# untitled.net
KiCad netlist of a schematic drawn in EAGLE
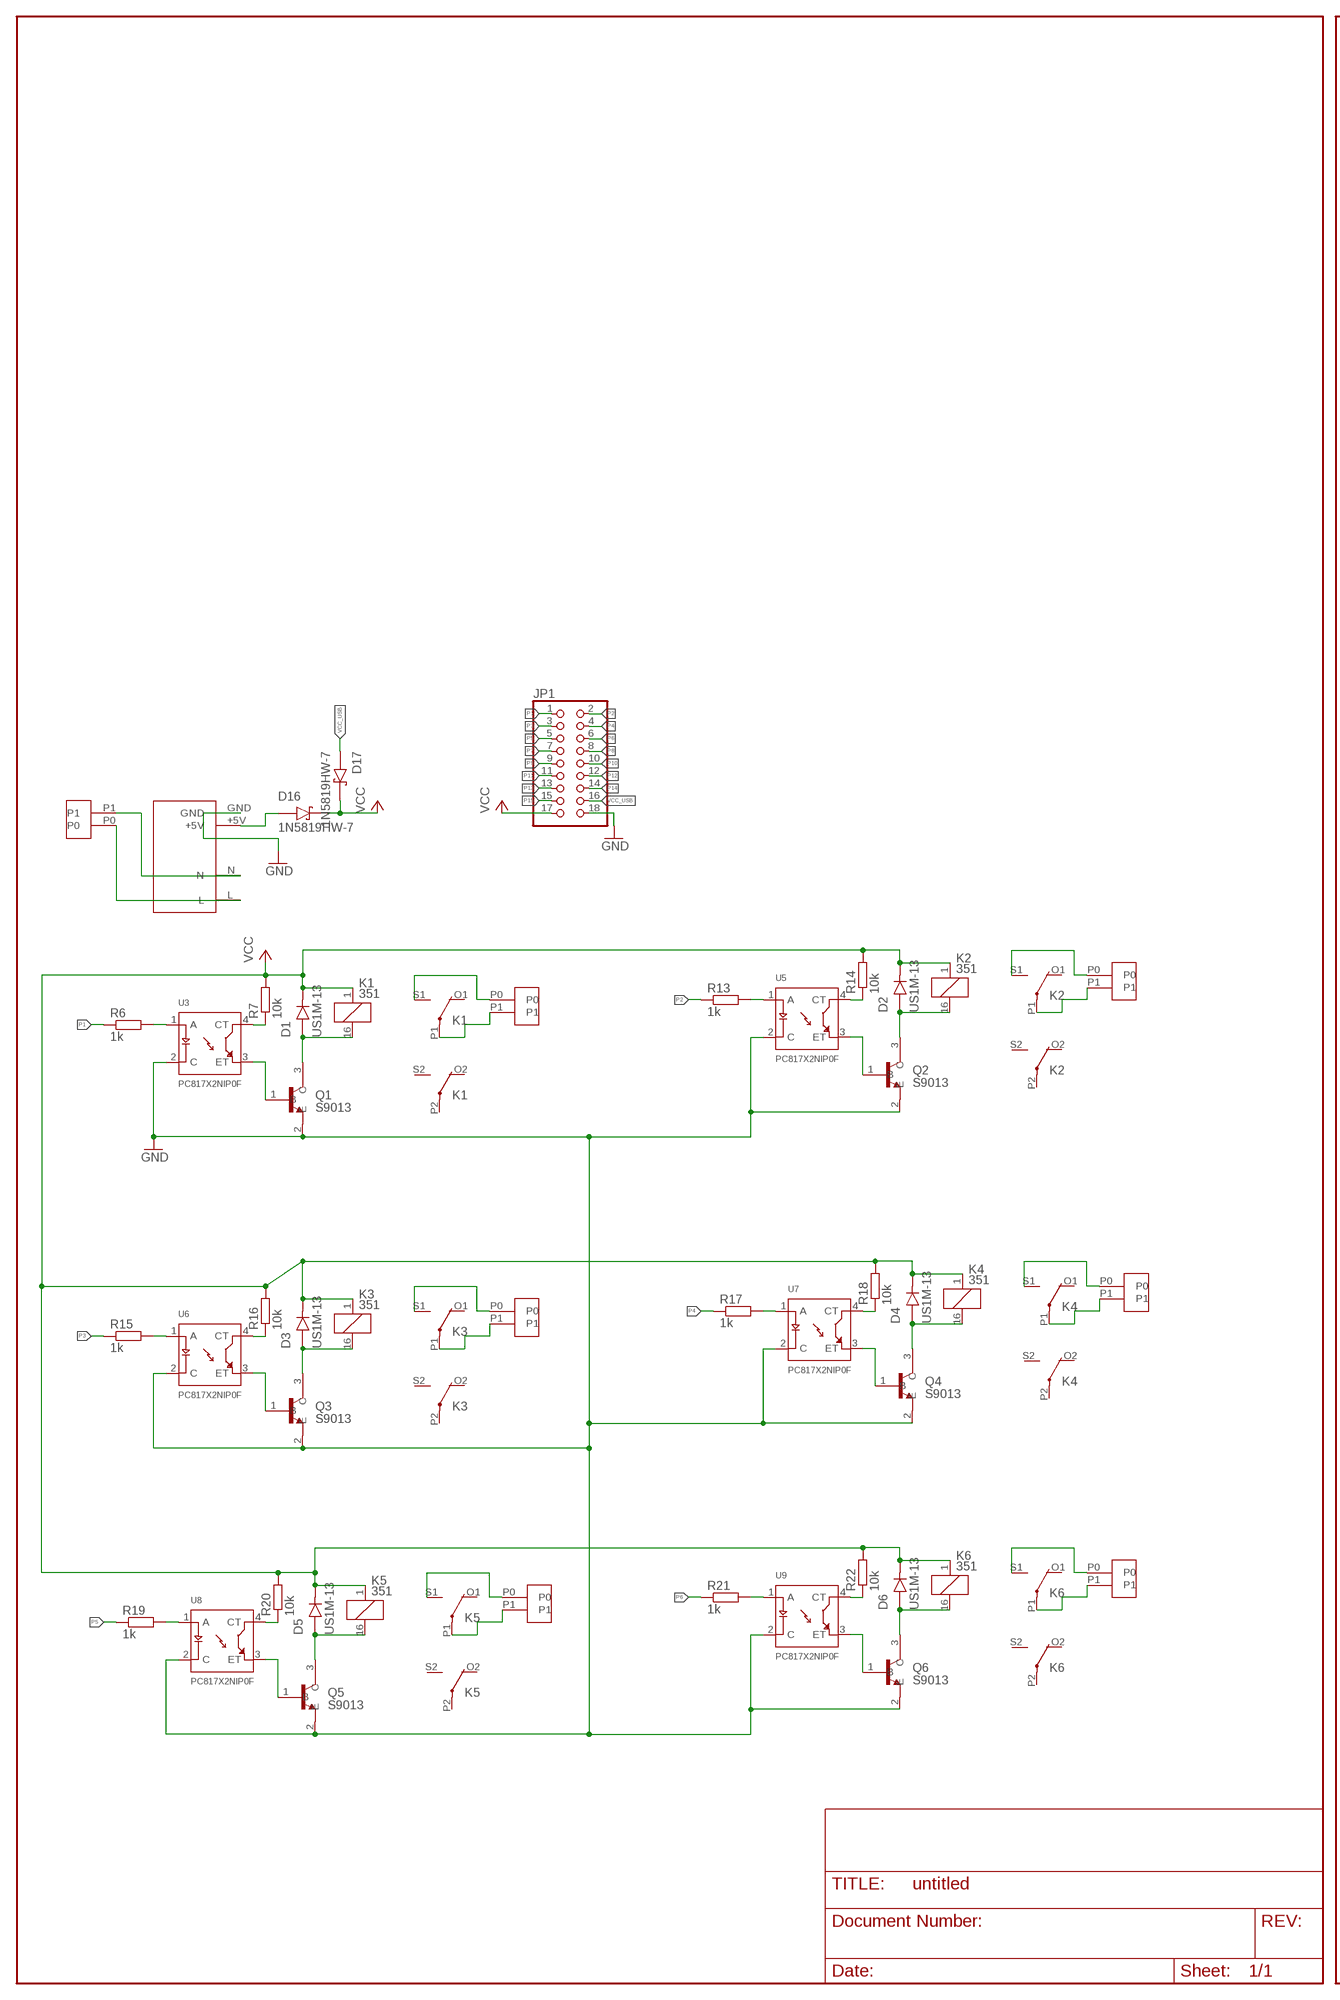
[diagram p0: schematic, sheet 1, part 1 of 2]
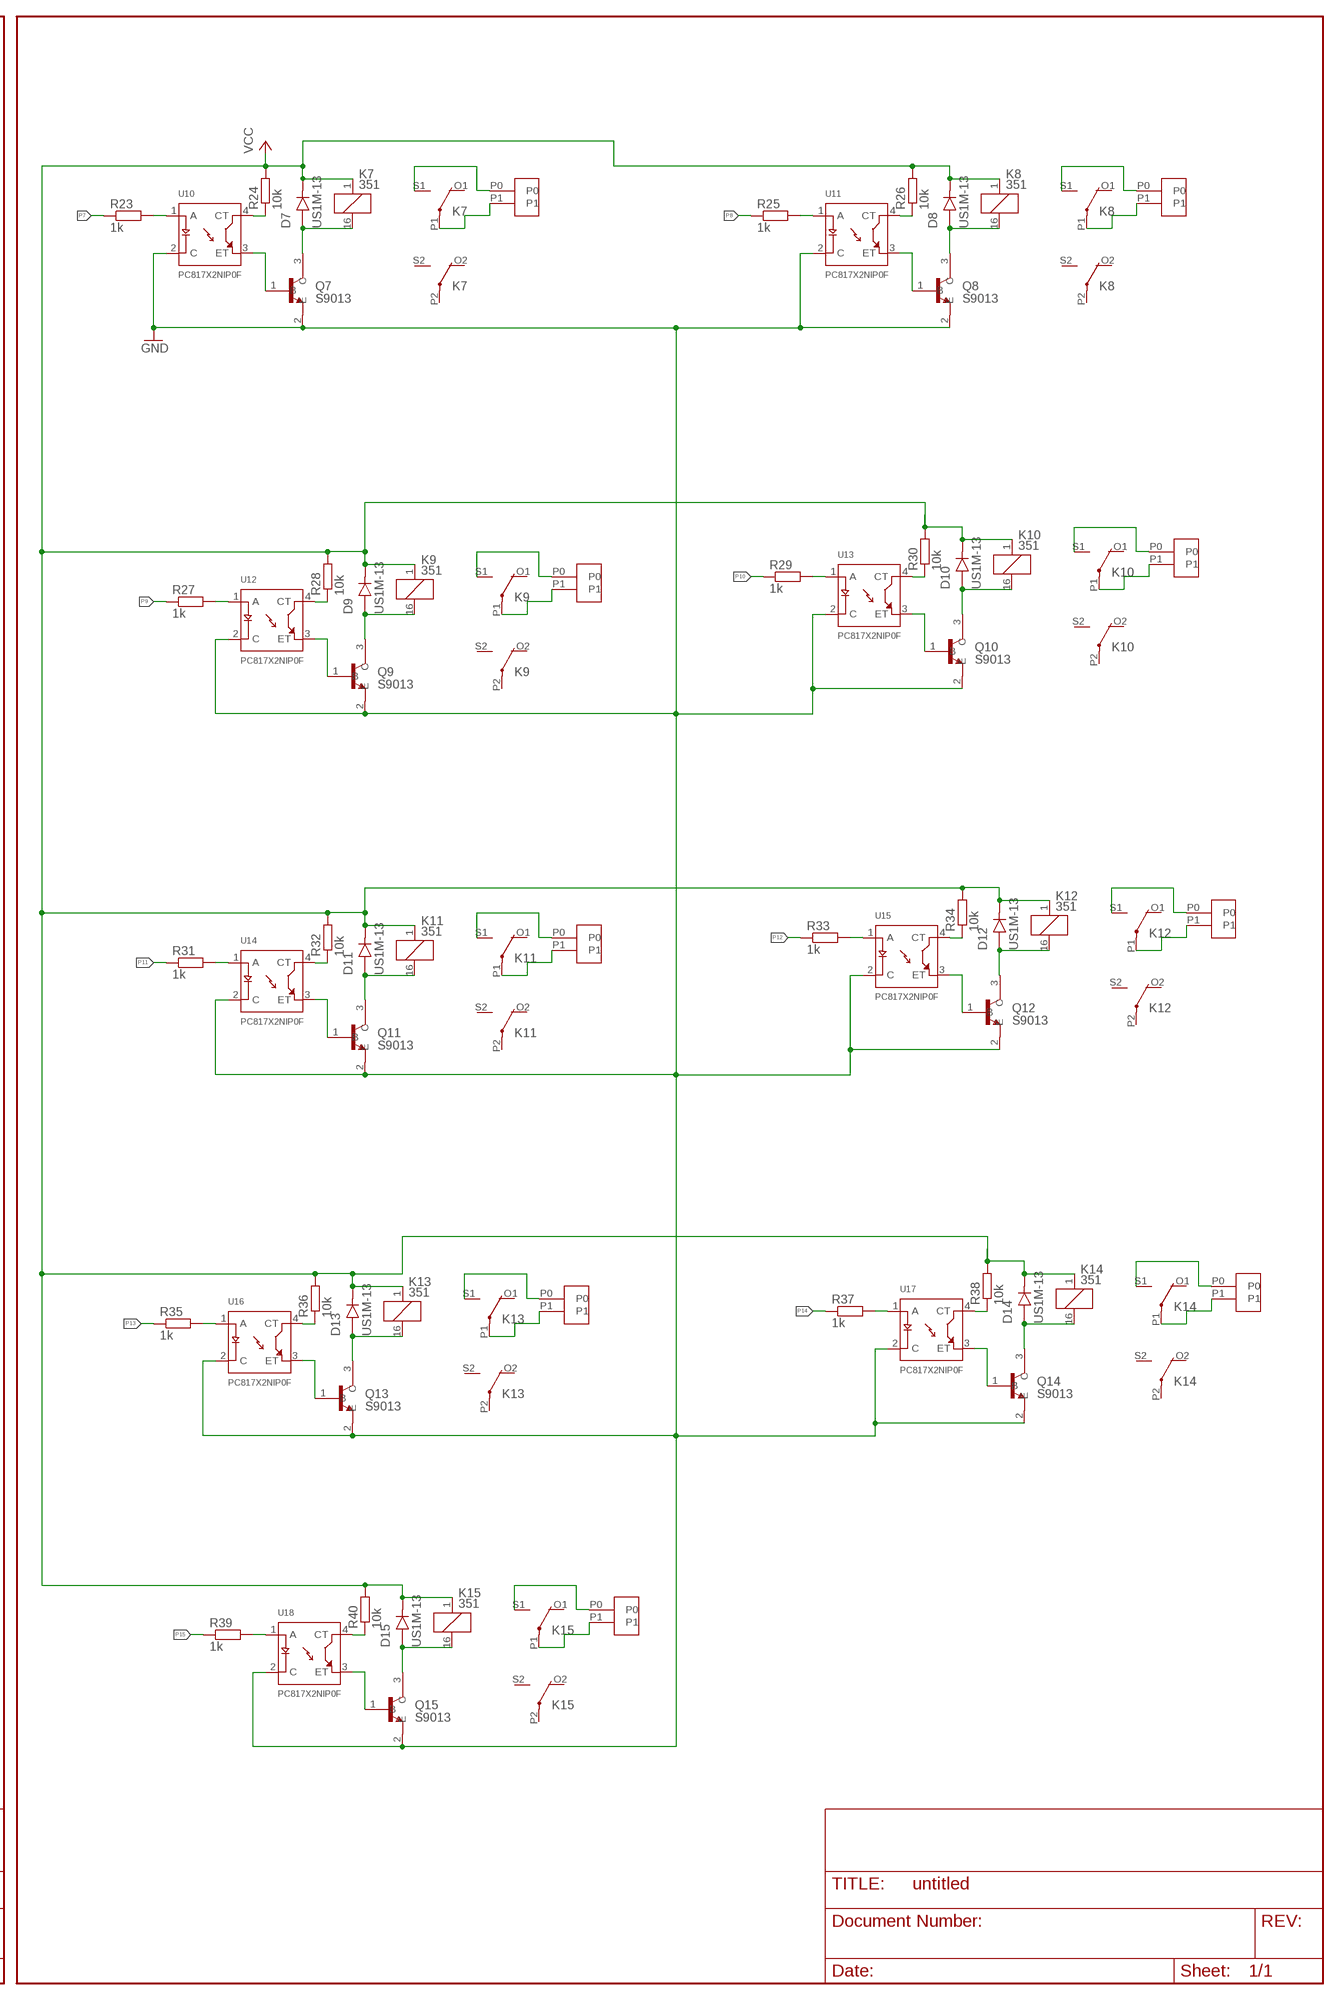
[diagram p1: schematic, sheet 1, part 2 of 2]

(export (version "E")
  (design (tool "Eeschema 10.0.6"))
  (components
    (comp (ref "CONN2P-3.5PI1")
      (value "CONN2P-3.5PI")
      (footprint "eagle-import:CONN2P-3.5PI")
      (libsource (lib "eagle-import") (part "CONN2P-3.5PI"))
    )
    (comp (ref "CONN2P-3.5PI2")
      (value "CONN2P-3.5PI")
      (footprint "eagle-import:CONN2P-3.5PI")
      (libsource (lib "eagle-import") (part "CONN2P-3.5PI"))
    )
    (comp (ref "CONN2P-3.5PI3")
      (value "CONN2P-3.5PI")
      (footprint "eagle-import:CONN2P-3.5PI")
      (libsource (lib "eagle-import") (part "CONN2P-3.5PI"))
    )
    (comp (ref "CONN2P-3.5PI4")
      (value "CONN2P-3.5PI")
      (footprint "eagle-import:CONN2P-3.5PI")
      (libsource (lib "eagle-import") (part "CONN2P-3.5PI"))
    )
    (comp (ref "CONN2P-3.5PI5")
      (value "CONN2P-3.5PI")
      (footprint "eagle-import:CONN2P-3.5PI")
      (libsource (lib "eagle-import") (part "CONN2P-3.5PI"))
    )
    (comp (ref "CONN2P-3.5PI6")
      (value "CONN2P-3.5PI")
      (footprint "eagle-import:CONN2P-3.5PI")
      (libsource (lib "eagle-import") (part "CONN2P-3.5PI"))
    )
    (comp (ref "CONN2P-3.5PI7")
      (value "CONN2P-3.5PI")
      (footprint "eagle-import:CONN2P-3.5PI")
      (libsource (lib "eagle-import") (part "CONN2P-3.5PI"))
    )
    (comp (ref "CONN2P-3.5PI8")
      (value "CONN2P-3.5PI")
      (footprint "eagle-import:CONN2P-3.5PI")
      (libsource (lib "eagle-import") (part "CONN2P-3.5PI"))
    )
    (comp (ref "CONN2P-3.5PI9")
      (value "CONN2P-3.5PI")
      (footprint "eagle-import:CONN2P-3.5PI")
      (libsource (lib "eagle-import") (part "CONN2P-3.5PI"))
    )
    (comp (ref "CONN2P-3.5PI10")
      (value "CONN2P-3.5PI")
      (footprint "eagle-import:CONN2P-3.5PI")
      (libsource (lib "eagle-import") (part "CONN2P-3.5PI"))
    )
    (comp (ref "CONN2P-3.5PI11")
      (value "CONN2P-3.5PI")
      (footprint "eagle-import:CONN2P-3.5PI")
      (libsource (lib "eagle-import") (part "CONN2P-3.5PI"))
    )
    (comp (ref "CONN2P-3.5PI12")
      (value "CONN2P-3.5PI")
      (footprint "eagle-import:CONN2P-3.5PI")
      (libsource (lib "eagle-import") (part "CONN2P-3.5PI"))
    )
    (comp (ref "CONN2P-3.5PI13")
      (value "CONN2P-3.5PI")
      (footprint "eagle-import:CONN2P-3.5PI")
      (libsource (lib "eagle-import") (part "CONN2P-3.5PI"))
    )
    (comp (ref "CONN2P-3.5PI14")
      (value "CONN2P-3.5PI")
      (footprint "eagle-import:CONN2P-3.5PI")
      (libsource (lib "eagle-import") (part "CONN2P-3.5PI"))
    )
    (comp (ref "CONN2P-3.5PI15")
      (value "CONN2P-3.5PI")
      (footprint "eagle-import:CONN2P-3.5PI")
      (libsource (lib "eagle-import") (part "CONN2P-3.5PI"))
    )
    (comp (ref "CONN2P-3.5PI16")
      (value "CONN2P-3.5PI")
      (footprint "eagle-import:CONN2P-3.5PI")
      (libsource (lib "eagle-import") (part "CONN2P-3.5PI"))
    )
    (comp (ref "D1")
      (value "US1M-13")
      (footprint "eagle-import:DIOM5226X240N")
      (fields (field (name "MF") "Diodes Incorporated"))
      (libsource (lib "eagle-import") (part "US1M-13"))
    )
    (comp (ref "D2")
      (value "US1M-13")
      (footprint "eagle-import:DIOM5226X240N")
      (fields (field (name "MF") "Diodes Incorporated"))
      (libsource (lib "eagle-import") (part "US1M-13"))
    )
    (comp (ref "D3")
      (value "US1M-13")
      (footprint "eagle-import:DIOM5226X240N")
      (fields (field (name "MF") "Diodes Incorporated"))
      (libsource (lib "eagle-import") (part "US1M-13"))
    )
    (comp (ref "D4")
      (value "US1M-13")
      (footprint "eagle-import:DIOM5226X240N")
      (fields (field (name "MF") "Diodes Incorporated"))
      (libsource (lib "eagle-import") (part "US1M-13"))
    )
    (comp (ref "D5")
      (value "US1M-13")
      (footprint "eagle-import:DIOM5226X240N")
      (fields (field (name "MF") "Diodes Incorporated"))
      (libsource (lib "eagle-import") (part "US1M-13"))
    )
    (comp (ref "D6")
      (value "US1M-13")
      (footprint "eagle-import:DIOM5226X240N")
      (fields (field (name "MF") "Diodes Incorporated"))
      (libsource (lib "eagle-import") (part "US1M-13"))
    )
    (comp (ref "D7")
      (value "US1M-13")
      (footprint "eagle-import:DIOM5226X240N")
      (fields (field (name "MF") "Diodes Incorporated"))
      (libsource (lib "eagle-import") (part "US1M-13"))
    )
    (comp (ref "D8")
      (value "US1M-13")
      (footprint "eagle-import:DIOM5226X240N")
      (fields (field (name "MF") "Diodes Incorporated"))
      (libsource (lib "eagle-import") (part "US1M-13"))
    )
    (comp (ref "D9")
      (value "US1M-13")
      (footprint "eagle-import:DIOM5226X240N")
      (fields (field (name "MF") "Diodes Incorporated"))
      (libsource (lib "eagle-import") (part "US1M-13"))
    )
    (comp (ref "D10")
      (value "US1M-13")
      (footprint "eagle-import:DIOM5226X240N")
      (fields (field (name "MF") "Diodes Incorporated"))
      (libsource (lib "eagle-import") (part "US1M-13"))
    )
    (comp (ref "D11")
      (value "US1M-13")
      (footprint "eagle-import:DIOM5226X240N")
      (fields (field (name "MF") "Diodes Incorporated"))
      (libsource (lib "eagle-import") (part "US1M-13"))
    )
    (comp (ref "D12")
      (value "US1M-13")
      (footprint "eagle-import:DIOM5226X240N")
      (fields (field (name "MF") "Diodes Incorporated"))
      (libsource (lib "eagle-import") (part "US1M-13"))
    )
    (comp (ref "D13")
      (value "US1M-13")
      (footprint "eagle-import:DIOM5226X240N")
      (fields (field (name "MF") "Diodes Incorporated"))
      (libsource (lib "eagle-import") (part "US1M-13"))
    )
    (comp (ref "D14")
      (value "US1M-13")
      (footprint "eagle-import:DIOM5226X240N")
      (fields (field (name "MF") "Diodes Incorporated"))
      (libsource (lib "eagle-import") (part "US1M-13"))
    )
    (comp (ref "D15")
      (value "US1M-13")
      (footprint "eagle-import:DIOM5226X240N")
      (fields (field (name "MF") "Diodes Incorporated"))
      (libsource (lib "eagle-import") (part "US1M-13"))
    )
    (comp (ref "D16")
      (value "1N5819HW-7")
      (footprint "eagle-import:SOD3715X145N")
      (fields (field (name "MF") "Diodes Inc."))
      (libsource (lib "eagle-import") (part "1N5819HW-7"))
    )
    (comp (ref "D17")
      (value "1N5819HW-7")
      (footprint "eagle-import:SOD3715X145N")
      (fields (field (name "MF") "Diodes Inc."))
      (libsource (lib "eagle-import") (part "1N5819HW-7"))
    )
    (comp (ref "JP1")
      (value "PINHD-2X9-CBIG")
      (footprint "eagle-import:2X09-CLEANBIG")
      (libsource (lib "eagle-import") (part "PINHD-2X9-CBIG"))
    )
    (comp (ref "K1")
      (value "351")
      (footprint "eagle-import:351")
      (libsource (lib "eagle-import") (part "351"))
    )
    (comp (ref "K2")
      (value "351")
      (footprint "eagle-import:351")
      (libsource (lib "eagle-import") (part "351"))
    )
    (comp (ref "K3")
      (value "351")
      (footprint "eagle-import:351")
      (libsource (lib "eagle-import") (part "351"))
    )
    (comp (ref "K4")
      (value "351")
      (footprint "eagle-import:351")
      (libsource (lib "eagle-import") (part "351"))
    )
    (comp (ref "K5")
      (value "351")
      (footprint "eagle-import:351")
      (libsource (lib "eagle-import") (part "351"))
    )
    (comp (ref "K6")
      (value "351")
      (footprint "eagle-import:351")
      (libsource (lib "eagle-import") (part "351"))
    )
    (comp (ref "K7")
      (value "351")
      (footprint "eagle-import:351")
      (libsource (lib "eagle-import") (part "351"))
    )
    (comp (ref "K8")
      (value "351")
      (footprint "eagle-import:351")
      (libsource (lib "eagle-import") (part "351"))
    )
    (comp (ref "K9")
      (value "351")
      (footprint "eagle-import:351")
      (libsource (lib "eagle-import") (part "351"))
    )
    (comp (ref "K10")
      (value "351")
      (footprint "eagle-import:351")
      (libsource (lib "eagle-import") (part "351"))
    )
    (comp (ref "K11")
      (value "351")
      (footprint "eagle-import:351")
      (libsource (lib "eagle-import") (part "351"))
    )
    (comp (ref "K12")
      (value "351")
      (footprint "eagle-import:351")
      (libsource (lib "eagle-import") (part "351"))
    )
    (comp (ref "K13")
      (value "351")
      (footprint "eagle-import:351")
      (libsource (lib "eagle-import") (part "351"))
    )
    (comp (ref "K14")
      (value "351")
      (footprint "eagle-import:351")
      (libsource (lib "eagle-import") (part "351"))
    )
    (comp (ref "K15")
      (value "351")
      (footprint "eagle-import:351")
      (libsource (lib "eagle-import") (part "351"))
    )
    (comp (ref "Q1")
      (value "S9013")
      (footprint "eagle-import:SOT95P240X120-3N")
      (fields (field (name "MF") "JCET"))
      (libsource (lib "eagle-import") (part "S9013"))
    )
    (comp (ref "Q2")
      (value "S9013")
      (footprint "eagle-import:SOT95P240X120-3N")
      (fields (field (name "MF") "JCET"))
      (libsource (lib "eagle-import") (part "S9013"))
    )
    (comp (ref "Q3")
      (value "S9013")
      (footprint "eagle-import:SOT95P240X120-3N")
      (fields (field (name "MF") "JCET"))
      (libsource (lib "eagle-import") (part "S9013"))
    )
    (comp (ref "Q4")
      (value "S9013")
      (footprint "eagle-import:SOT95P240X120-3N")
      (fields (field (name "MF") "JCET"))
      (libsource (lib "eagle-import") (part "S9013"))
    )
    (comp (ref "Q5")
      (value "S9013")
      (footprint "eagle-import:SOT95P240X120-3N")
      (fields (field (name "MF") "JCET"))
      (libsource (lib "eagle-import") (part "S9013"))
    )
    (comp (ref "Q6")
      (value "S9013")
      (footprint "eagle-import:SOT95P240X120-3N")
      (fields (field (name "MF") "JCET"))
      (libsource (lib "eagle-import") (part "S9013"))
    )
    (comp (ref "Q7")
      (value "S9013")
      (footprint "eagle-import:SOT95P240X120-3N")
      (fields (field (name "MF") "JCET"))
      (libsource (lib "eagle-import") (part "S9013"))
    )
    (comp (ref "Q8")
      (value "S9013")
      (footprint "eagle-import:SOT95P240X120-3N")
      (fields (field (name "MF") "JCET"))
      (libsource (lib "eagle-import") (part "S9013"))
    )
    (comp (ref "Q9")
      (value "S9013")
      (footprint "eagle-import:SOT95P240X120-3N")
      (fields (field (name "MF") "JCET"))
      (libsource (lib "eagle-import") (part "S9013"))
    )
    (comp (ref "Q10")
      (value "S9013")
      (footprint "eagle-import:SOT95P240X120-3N")
      (fields (field (name "MF") "JCET"))
      (libsource (lib "eagle-import") (part "S9013"))
    )
    (comp (ref "Q11")
      (value "S9013")
      (footprint "eagle-import:SOT95P240X120-3N")
      (fields (field (name "MF") "JCET"))
      (libsource (lib "eagle-import") (part "S9013"))
    )
    (comp (ref "Q12")
      (value "S9013")
      (footprint "eagle-import:SOT95P240X120-3N")
      (fields (field (name "MF") "JCET"))
      (libsource (lib "eagle-import") (part "S9013"))
    )
    (comp (ref "Q13")
      (value "S9013")
      (footprint "eagle-import:SOT95P240X120-3N")
      (fields (field (name "MF") "JCET"))
      (libsource (lib "eagle-import") (part "S9013"))
    )
    (comp (ref "Q14")
      (value "S9013")
      (footprint "eagle-import:SOT95P240X120-3N")
      (fields (field (name "MF") "JCET"))
      (libsource (lib "eagle-import") (part "S9013"))
    )
    (comp (ref "Q15")
      (value "S9013")
      (footprint "eagle-import:SOT95P240X120-3N")
      (fields (field (name "MF") "JCET"))
      (libsource (lib "eagle-import") (part "S9013"))
    )
    (comp (ref "R6")
      (value "1k")
      (footprint "eagle-import:R0805")
      (libsource (lib "eagle-import") (part "R-EU_R0805"))
    )
    (comp (ref "R7")
      (value "10k")
      (footprint "eagle-import:R0805")
      (libsource (lib "eagle-import") (part "R-EU_R0805"))
    )
    (comp (ref "R13")
      (value "1k")
      (footprint "eagle-import:R0805")
      (libsource (lib "eagle-import") (part "R-EU_R0805"))
    )
    (comp (ref "R14")
      (value "10k")
      (footprint "eagle-import:R0805")
      (libsource (lib "eagle-import") (part "R-EU_R0805"))
    )
    (comp (ref "R15")
      (value "1k")
      (footprint "eagle-import:R0805")
      (libsource (lib "eagle-import") (part "R-EU_R0805"))
    )
    (comp (ref "R16")
      (value "10k")
      (footprint "eagle-import:R0805")
      (libsource (lib "eagle-import") (part "R-EU_R0805"))
    )
    (comp (ref "R17")
      (value "1k")
      (footprint "eagle-import:R0805")
      (libsource (lib "eagle-import") (part "R-EU_R0805"))
    )
    (comp (ref "R18")
      (value "10k")
      (footprint "eagle-import:R0805")
      (libsource (lib "eagle-import") (part "R-EU_R0805"))
    )
    (comp (ref "R19")
      (value "1k")
      (footprint "eagle-import:R0805")
      (libsource (lib "eagle-import") (part "R-EU_R0805"))
    )
    (comp (ref "R20")
      (value "10k")
      (footprint "eagle-import:R0805")
      (libsource (lib "eagle-import") (part "R-EU_R0805"))
    )
    (comp (ref "R21")
      (value "1k")
      (footprint "eagle-import:R0805")
      (libsource (lib "eagle-import") (part "R-EU_R0805"))
    )
    (comp (ref "R22")
      (value "10k")
      (footprint "eagle-import:R0805")
      (libsource (lib "eagle-import") (part "R-EU_R0805"))
    )
    (comp (ref "R23")
      (value "1k")
      (footprint "eagle-import:R0805")
      (libsource (lib "eagle-import") (part "R-EU_R0805"))
    )
    (comp (ref "R24")
      (value "10k")
      (footprint "eagle-import:R0805")
      (libsource (lib "eagle-import") (part "R-EU_R0805"))
    )
    (comp (ref "R25")
      (value "1k")
      (footprint "eagle-import:R0805")
      (libsource (lib "eagle-import") (part "R-EU_R0805"))
    )
    (comp (ref "R26")
      (value "10k")
      (footprint "eagle-import:R0805")
      (libsource (lib "eagle-import") (part "R-EU_R0805"))
    )
    (comp (ref "R27")
      (value "1k")
      (footprint "eagle-import:R0805")
      (libsource (lib "eagle-import") (part "R-EU_R0805"))
    )
    (comp (ref "R28")
      (value "10k")
      (footprint "eagle-import:R0805")
      (libsource (lib "eagle-import") (part "R-EU_R0805"))
    )
    (comp (ref "R29")
      (value "1k")
      (footprint "eagle-import:R0805")
      (libsource (lib "eagle-import") (part "R-EU_R0805"))
    )
    (comp (ref "R30")
      (value "10k")
      (footprint "eagle-import:R0805")
      (libsource (lib "eagle-import") (part "R-EU_R0805"))
    )
    (comp (ref "R31")
      (value "1k")
      (footprint "eagle-import:R0805")
      (libsource (lib "eagle-import") (part "R-EU_R0805"))
    )
    (comp (ref "R32")
      (value "10k")
      (footprint "eagle-import:R0805")
      (libsource (lib "eagle-import") (part "R-EU_R0805"))
    )
    (comp (ref "R33")
      (value "1k")
      (footprint "eagle-import:R0805")
      (libsource (lib "eagle-import") (part "R-EU_R0805"))
    )
    (comp (ref "R34")
      (value "10k")
      (footprint "eagle-import:R0805")
      (libsource (lib "eagle-import") (part "R-EU_R0805"))
    )
    (comp (ref "R35")
      (value "1k")
      (footprint "eagle-import:R0805")
      (libsource (lib "eagle-import") (part "R-EU_R0805"))
    )
    (comp (ref "R36")
      (value "10k")
      (footprint "eagle-import:R0805")
      (libsource (lib "eagle-import") (part "R-EU_R0805"))
    )
    (comp (ref "R37")
      (value "1k")
      (footprint "eagle-import:R0805")
      (libsource (lib "eagle-import") (part "R-EU_R0805"))
    )
    (comp (ref "R38")
      (value "10k")
      (footprint "eagle-import:R0805")
      (libsource (lib "eagle-import") (part "R-EU_R0805"))
    )
    (comp (ref "R39")
      (value "1k")
      (footprint "eagle-import:R0805")
      (libsource (lib "eagle-import") (part "R-EU_R0805"))
    )
    (comp (ref "R40")
      (value "10k")
      (footprint "eagle-import:R0805")
      (libsource (lib "eagle-import") (part "R-EU_R0805"))
    )
    (comp (ref "U3")
      (value "PC817X2NIP0F")
      (footprint "eagle-import:SOT254P975X400-4N")
      (fields (field (name "MF") "Sharp Microelectronics"))
      (libsource (lib "eagle-import") (part "PC817X2NIP0F"))
    )
    (comp (ref "U5")
      (value "PC817X2NIP0F")
      (footprint "eagle-import:SOT254P975X400-4N")
      (fields (field (name "MF") "Sharp Microelectronics"))
      (libsource (lib "eagle-import") (part "PC817X2NIP0F"))
    )
    (comp (ref "U6")
      (value "PC817X2NIP0F")
      (footprint "eagle-import:SOT254P975X400-4N")
      (fields (field (name "MF") "Sharp Microelectronics"))
      (libsource (lib "eagle-import") (part "PC817X2NIP0F"))
    )
    (comp (ref "U7")
      (value "PC817X2NIP0F")
      (footprint "eagle-import:SOT254P975X400-4N")
      (fields (field (name "MF") "Sharp Microelectronics"))
      (libsource (lib "eagle-import") (part "PC817X2NIP0F"))
    )
    (comp (ref "U8")
      (value "PC817X2NIP0F")
      (footprint "eagle-import:SOT254P975X400-4N")
      (fields (field (name "MF") "Sharp Microelectronics"))
      (libsource (lib "eagle-import") (part "PC817X2NIP0F"))
    )
    (comp (ref "U9")
      (value "PC817X2NIP0F")
      (footprint "eagle-import:SOT254P975X400-4N")
      (fields (field (name "MF") "Sharp Microelectronics"))
      (libsource (lib "eagle-import") (part "PC817X2NIP0F"))
    )
    (comp (ref "U10")
      (value "PC817X2NIP0F")
      (footprint "eagle-import:SOT254P975X400-4N")
      (fields (field (name "MF") "Sharp Microelectronics"))
      (libsource (lib "eagle-import") (part "PC817X2NIP0F"))
    )
    (comp (ref "U11")
      (value "PC817X2NIP0F")
      (footprint "eagle-import:SOT254P975X400-4N")
      (fields (field (name "MF") "Sharp Microelectronics"))
      (libsource (lib "eagle-import") (part "PC817X2NIP0F"))
    )
    (comp (ref "U12")
      (value "PC817X2NIP0F")
      (footprint "eagle-import:SOT254P975X400-4N")
      (fields (field (name "MF") "Sharp Microelectronics"))
      (libsource (lib "eagle-import") (part "PC817X2NIP0F"))
    )
    (comp (ref "U13")
      (value "PC817X2NIP0F")
      (footprint "eagle-import:SOT254P975X400-4N")
      (fields (field (name "MF") "Sharp Microelectronics"))
      (libsource (lib "eagle-import") (part "PC817X2NIP0F"))
    )
    (comp (ref "U14")
      (value "PC817X2NIP0F")
      (footprint "eagle-import:SOT254P975X400-4N")
      (fields (field (name "MF") "Sharp Microelectronics"))
      (libsource (lib "eagle-import") (part "PC817X2NIP0F"))
    )
    (comp (ref "U15")
      (value "PC817X2NIP0F")
      (footprint "eagle-import:SOT254P975X400-4N")
      (fields (field (name "MF") "Sharp Microelectronics"))
      (libsource (lib "eagle-import") (part "PC817X2NIP0F"))
    )
    (comp (ref "U16")
      (value "PC817X2NIP0F")
      (footprint "eagle-import:SOT254P975X400-4N")
      (fields (field (name "MF") "Sharp Microelectronics"))
      (libsource (lib "eagle-import") (part "PC817X2NIP0F"))
    )
    (comp (ref "U17")
      (value "PC817X2NIP0F")
      (footprint "eagle-import:SOT254P975X400-4N")
      (fields (field (name "MF") "Sharp Microelectronics"))
      (libsource (lib "eagle-import") (part "PC817X2NIP0F"))
    )
    (comp (ref "U18")
      (value "PC817X2NIP0F")
      (footprint "eagle-import:SOT254P975X400-4N")
      (fields (field (name "MF") "Sharp Microelectronics"))
      (libsource (lib "eagle-import") (part "PC817X2NIP0F"))
    )
    (comp (ref "WX-DC1")
      (value "WX-DC12003")
      (footprint "eagle-import:WX-DC12003")
      (libsource (lib "eagle-import") (part "WX-DC12003"))
    )
  )
  (nets
    (net (code "1") (name "GND") (class "Default")
      (node (ref "JP1") (pin "18") (pinfunction "18_18") (pintype "passive"))
      (node (ref "Q1") (pin "2") (pinfunction "E_2") (pintype "passive"))
      (node (ref "Q10") (pin "2") (pinfunction "E_2") (pintype "passive"))
      (node (ref "Q11") (pin "2") (pinfunction "E_2") (pintype "passive"))
      (node (ref "Q12") (pin "2") (pinfunction "E_2") (pintype "passive"))
      (node (ref "Q13") (pin "2") (pinfunction "E_2") (pintype "passive"))
      (node (ref "Q14") (pin "2") (pinfunction "E_2") (pintype "passive"))
      (node (ref "Q15") (pin "2") (pinfunction "E_2") (pintype "passive"))
      (node (ref "Q2") (pin "2") (pinfunction "E_2") (pintype "passive"))
      (node (ref "Q3") (pin "2") (pinfunction "E_2") (pintype "passive"))
      (node (ref "Q4") (pin "2") (pinfunction "E_2") (pintype "passive"))
      (node (ref "Q5") (pin "2") (pinfunction "E_2") (pintype "passive"))
      (node (ref "Q6") (pin "2") (pinfunction "E_2") (pintype "passive"))
      (node (ref "Q7") (pin "2") (pinfunction "E_2") (pintype "passive"))
      (node (ref "Q8") (pin "2") (pinfunction "E_2") (pintype "passive"))
      (node (ref "Q9") (pin "2") (pinfunction "E_2") (pintype "passive"))
      (node (ref "U10") (pin "2") (pinfunction "C_2") (pintype "passive"))
      (node (ref "U11") (pin "2") (pinfunction "C_2") (pintype "passive"))
      (node (ref "U12") (pin "2") (pinfunction "C_2") (pintype "passive"))
      (node (ref "U13") (pin "2") (pinfunction "C_2") (pintype "passive"))
      (node (ref "U14") (pin "2") (pinfunction "C_2") (pintype "passive"))
      (node (ref "U15") (pin "2") (pinfunction "C_2") (pintype "passive"))
      (node (ref "U16") (pin "2") (pinfunction "C_2") (pintype "passive"))
      (node (ref "U17") (pin "2") (pinfunction "C_2") (pintype "passive"))
      (node (ref "U18") (pin "2") (pinfunction "C_2") (pintype "passive"))
      (node (ref "U3") (pin "2") (pinfunction "C_2") (pintype "passive"))
      (node (ref "U5") (pin "2") (pinfunction "C_2") (pintype "passive"))
      (node (ref "U6") (pin "2") (pinfunction "C_2") (pintype "passive"))
      (node (ref "U7") (pin "2") (pinfunction "C_2") (pintype "passive"))
      (node (ref "U8") (pin "2") (pinfunction "C_2") (pintype "passive"))
      (node (ref "U9") (pin "2") (pinfunction "C_2") (pintype "passive"))
      (node (ref "WX-DC1") (pin "GND") (pinfunction "GND_GND") (pintype "bidirectional"))
    )
    (net (code "2") (name "Net-(CONN2P-3.5PI1-PadP0)") (class "Default")
      (node (ref "CONN2P-3.5PI1") (pin "P0") (pinfunction "P0_P0") (pintype "bidirectional"))
      (node (ref "WX-DC1") (pin "L") (pinfunction "L_L") (pintype "bidirectional"))
    )
    (net (code "3") (name "Net-(CONN2P-3.5PI1-PadP1)") (class "Default")
      (node (ref "CONN2P-3.5PI1") (pin "P1") (pinfunction "P1_P1") (pintype "bidirectional"))
      (node (ref "WX-DC1") (pin "N") (pinfunction "N_N") (pintype "bidirectional"))
    )
    (net (code "4") (name "Net-(D16-PadA)") (class "Default")
      (node (ref "D16") (pin "A") (pinfunction "A_A") (pintype "passive"))
      (node (ref "WX-DC1") (pin "+5V") (pinfunction "+5V_+5V") (pintype "bidirectional"))
    )
    (net (code "5") (name "Net-(K1A-2)") (class "Default")
      (node (ref "D1") (pin "A") (pinfunction "A_A") (pintype "passive"))
      (node (ref "K1") (pin "16") (pinfunction "2_16") (pintype "passive"))
      (node (ref "Q1") (pin "3") (pinfunction "C_3") (pintype "passive"))
    )
    (net (code "6") (name "Net-(K1B-P)") (class "Default")
      (node (ref "CONN2P-3.5PI15") (pin "P1") (pinfunction "P1_P1") (pintype "bidirectional"))
      (node (ref "K1") (pin "P1") (pinfunction "P_P1") (pintype "passive"))
    )
    (net (code "7") (name "Net-(K1B-S)") (class "Default")
      (node (ref "CONN2P-3.5PI15") (pin "P0") (pinfunction "P0_P0") (pintype "bidirectional"))
      (node (ref "K1") (pin "S1") (pinfunction "S_S1") (pintype "passive"))
    )
    (net (code "8") (name "Net-(K2A-2)") (class "Default")
      (node (ref "D2") (pin "A") (pinfunction "A_A") (pintype "passive"))
      (node (ref "K2") (pin "16") (pinfunction "2_16") (pintype "passive"))
      (node (ref "Q2") (pin "3") (pinfunction "C_3") (pintype "passive"))
    )
    (net (code "9") (name "Net-(K2B-P)") (class "Default")
      (node (ref "CONN2P-3.5PI16") (pin "P1") (pinfunction "P1_P1") (pintype "bidirectional"))
      (node (ref "K2") (pin "P1") (pinfunction "P_P1") (pintype "passive"))
    )
    (net (code "10") (name "Net-(K2B-S)") (class "Default")
      (node (ref "CONN2P-3.5PI16") (pin "P0") (pinfunction "P0_P0") (pintype "bidirectional"))
      (node (ref "K2") (pin "S1") (pinfunction "S_S1") (pintype "passive"))
    )
    (net (code "11") (name "Net-(K3A-2)") (class "Default")
      (node (ref "D3") (pin "A") (pinfunction "A_A") (pintype "passive"))
      (node (ref "K3") (pin "16") (pinfunction "2_16") (pintype "passive"))
      (node (ref "Q3") (pin "3") (pinfunction "C_3") (pintype "passive"))
    )
    (net (code "12") (name "Net-(K3B-P)") (class "Default")
      (node (ref "CONN2P-3.5PI2") (pin "P1") (pinfunction "P1_P1") (pintype "bidirectional"))
      (node (ref "K3") (pin "P1") (pinfunction "P_P1") (pintype "passive"))
    )
    (net (code "13") (name "Net-(K3B-S)") (class "Default")
      (node (ref "CONN2P-3.5PI2") (pin "P0") (pinfunction "P0_P0") (pintype "bidirectional"))
      (node (ref "K3") (pin "S1") (pinfunction "S_S1") (pintype "passive"))
    )
    (net (code "14") (name "Net-(K4A-2)") (class "Default")
      (node (ref "D4") (pin "A") (pinfunction "A_A") (pintype "passive"))
      (node (ref "K4") (pin "16") (pinfunction "2_16") (pintype "passive"))
      (node (ref "Q4") (pin "3") (pinfunction "C_3") (pintype "passive"))
    )
    (net (code "15") (name "Net-(K4B-P)") (class "Default")
      (node (ref "CONN2P-3.5PI3") (pin "P1") (pinfunction "P1_P1") (pintype "bidirectional"))
      (node (ref "K4") (pin "P1") (pinfunction "P_P1") (pintype "passive"))
    )
    (net (code "16") (name "Net-(K4B-S)") (class "Default")
      (node (ref "CONN2P-3.5PI3") (pin "P0") (pinfunction "P0_P0") (pintype "bidirectional"))
      (node (ref "K4") (pin "S1") (pinfunction "S_S1") (pintype "passive"))
    )
    (net (code "17") (name "Net-(K5A-2)") (class "Default")
      (node (ref "D5") (pin "A") (pinfunction "A_A") (pintype "passive"))
      (node (ref "K5") (pin "16") (pinfunction "2_16") (pintype "passive"))
      (node (ref "Q5") (pin "3") (pinfunction "C_3") (pintype "passive"))
    )
    (net (code "18") (name "Net-(K5B-P)") (class "Default")
      (node (ref "CONN2P-3.5PI4") (pin "P1") (pinfunction "P1_P1") (pintype "bidirectional"))
      (node (ref "K5") (pin "P1") (pinfunction "P_P1") (pintype "passive"))
    )
    (net (code "19") (name "Net-(K5B-S)") (class "Default")
      (node (ref "CONN2P-3.5PI4") (pin "P0") (pinfunction "P0_P0") (pintype "bidirectional"))
      (node (ref "K5") (pin "S1") (pinfunction "S_S1") (pintype "passive"))
    )
    (net (code "20") (name "Net-(K6A-2)") (class "Default")
      (node (ref "D6") (pin "A") (pinfunction "A_A") (pintype "passive"))
      (node (ref "K6") (pin "16") (pinfunction "2_16") (pintype "passive"))
      (node (ref "Q6") (pin "3") (pinfunction "C_3") (pintype "passive"))
    )
    (net (code "21") (name "Net-(K6B-P)") (class "Default")
      (node (ref "CONN2P-3.5PI5") (pin "P1") (pinfunction "P1_P1") (pintype "bidirectional"))
      (node (ref "K6") (pin "P1") (pinfunction "P_P1") (pintype "passive"))
    )
    (net (code "22") (name "Net-(K6B-S)") (class "Default")
      (node (ref "CONN2P-3.5PI5") (pin "P0") (pinfunction "P0_P0") (pintype "bidirectional"))
      (node (ref "K6") (pin "S1") (pinfunction "S_S1") (pintype "passive"))
    )
    (net (code "23") (name "Net-(K7A-2)") (class "Default")
      (node (ref "D7") (pin "A") (pinfunction "A_A") (pintype "passive"))
      (node (ref "K7") (pin "16") (pinfunction "2_16") (pintype "passive"))
      (node (ref "Q7") (pin "3") (pinfunction "C_3") (pintype "passive"))
    )
    (net (code "24") (name "Net-(K7B-P)") (class "Default")
      (node (ref "CONN2P-3.5PI6") (pin "P1") (pinfunction "P1_P1") (pintype "bidirectional"))
      (node (ref "K7") (pin "P1") (pinfunction "P_P1") (pintype "passive"))
    )
    (net (code "25") (name "Net-(K7B-S)") (class "Default")
      (node (ref "CONN2P-3.5PI6") (pin "P0") (pinfunction "P0_P0") (pintype "bidirectional"))
      (node (ref "K7") (pin "S1") (pinfunction "S_S1") (pintype "passive"))
    )
    (net (code "26") (name "Net-(K8A-2)") (class "Default")
      (node (ref "D8") (pin "A") (pinfunction "A_A") (pintype "passive"))
      (node (ref "K8") (pin "16") (pinfunction "2_16") (pintype "passive"))
      (node (ref "Q8") (pin "3") (pinfunction "C_3") (pintype "passive"))
    )
    (net (code "27") (name "Net-(K8B-P)") (class "Default")
      (node (ref "CONN2P-3.5PI7") (pin "P1") (pinfunction "P1_P1") (pintype "bidirectional"))
      (node (ref "K8") (pin "P1") (pinfunction "P_P1") (pintype "passive"))
    )
    (net (code "28") (name "Net-(K8B-S)") (class "Default")
      (node (ref "CONN2P-3.5PI7") (pin "P0") (pinfunction "P0_P0") (pintype "bidirectional"))
      (node (ref "K8") (pin "S1") (pinfunction "S_S1") (pintype "passive"))
    )
    (net (code "29") (name "Net-(K9A-2)") (class "Default")
      (node (ref "D9") (pin "A") (pinfunction "A_A") (pintype "passive"))
      (node (ref "K9") (pin "16") (pinfunction "2_16") (pintype "passive"))
      (node (ref "Q9") (pin "3") (pinfunction "C_3") (pintype "passive"))
    )
    (net (code "30") (name "Net-(K9B-P)") (class "Default")
      (node (ref "CONN2P-3.5PI8") (pin "P1") (pinfunction "P1_P1") (pintype "bidirectional"))
      (node (ref "K9") (pin "P1") (pinfunction "P_P1") (pintype "passive"))
    )
    (net (code "31") (name "Net-(K9B-S)") (class "Default")
      (node (ref "CONN2P-3.5PI8") (pin "P0") (pinfunction "P0_P0") (pintype "bidirectional"))
      (node (ref "K9") (pin "S1") (pinfunction "S_S1") (pintype "passive"))
    )
    (net (code "32") (name "Net-(K10A-2)") (class "Default")
      (node (ref "D10") (pin "A") (pinfunction "A_A") (pintype "passive"))
      (node (ref "K10") (pin "16") (pinfunction "2_16") (pintype "passive"))
      (node (ref "Q10") (pin "3") (pinfunction "C_3") (pintype "passive"))
    )
    (net (code "33") (name "Net-(K10B-P)") (class "Default")
      (node (ref "CONN2P-3.5PI9") (pin "P1") (pinfunction "P1_P1") (pintype "bidirectional"))
      (node (ref "K10") (pin "P1") (pinfunction "P_P1") (pintype "passive"))
    )
    (net (code "34") (name "Net-(K10B-S)") (class "Default")
      (node (ref "CONN2P-3.5PI9") (pin "P0") (pinfunction "P0_P0") (pintype "bidirectional"))
      (node (ref "K10") (pin "S1") (pinfunction "S_S1") (pintype "passive"))
    )
    (net (code "35") (name "Net-(K11A-2)") (class "Default")
      (node (ref "D11") (pin "A") (pinfunction "A_A") (pintype "passive"))
      (node (ref "K11") (pin "16") (pinfunction "2_16") (pintype "passive"))
      (node (ref "Q11") (pin "3") (pinfunction "C_3") (pintype "passive"))
    )
    (net (code "36") (name "Net-(K11B-P)") (class "Default")
      (node (ref "CONN2P-3.5PI10") (pin "P1") (pinfunction "P1_P1") (pintype "bidirectional"))
      (node (ref "K11") (pin "P1") (pinfunction "P_P1") (pintype "passive"))
    )
    (net (code "37") (name "Net-(K11B-S)") (class "Default")
      (node (ref "CONN2P-3.5PI10") (pin "P0") (pinfunction "P0_P0") (pintype "bidirectional"))
      (node (ref "K11") (pin "S1") (pinfunction "S_S1") (pintype "passive"))
    )
    (net (code "38") (name "Net-(K12A-2)") (class "Default")
      (node (ref "D12") (pin "A") (pinfunction "A_A") (pintype "passive"))
      (node (ref "K12") (pin "16") (pinfunction "2_16") (pintype "passive"))
      (node (ref "Q12") (pin "3") (pinfunction "C_3") (pintype "passive"))
    )
    (net (code "39") (name "Net-(K12B-P)") (class "Default")
      (node (ref "CONN2P-3.5PI11") (pin "P1") (pinfunction "P1_P1") (pintype "bidirectional"))
      (node (ref "K12") (pin "P1") (pinfunction "P_P1") (pintype "passive"))
    )
    (net (code "40") (name "Net-(K12B-S)") (class "Default")
      (node (ref "CONN2P-3.5PI11") (pin "P0") (pinfunction "P0_P0") (pintype "bidirectional"))
      (node (ref "K12") (pin "S1") (pinfunction "S_S1") (pintype "passive"))
    )
    (net (code "41") (name "Net-(K13A-2)") (class "Default")
      (node (ref "D13") (pin "A") (pinfunction "A_A") (pintype "passive"))
      (node (ref "K13") (pin "16") (pinfunction "2_16") (pintype "passive"))
      (node (ref "Q13") (pin "3") (pinfunction "C_3") (pintype "passive"))
    )
    (net (code "42") (name "Net-(K13B-P)") (class "Default")
      (node (ref "CONN2P-3.5PI12") (pin "P1") (pinfunction "P1_P1") (pintype "bidirectional"))
      (node (ref "K13") (pin "P1") (pinfunction "P_P1") (pintype "passive"))
    )
    (net (code "43") (name "Net-(K13B-S)") (class "Default")
      (node (ref "CONN2P-3.5PI12") (pin "P0") (pinfunction "P0_P0") (pintype "bidirectional"))
      (node (ref "K13") (pin "S1") (pinfunction "S_S1") (pintype "passive"))
    )
    (net (code "44") (name "Net-(K14A-2)") (class "Default")
      (node (ref "D14") (pin "A") (pinfunction "A_A") (pintype "passive"))
      (node (ref "K14") (pin "16") (pinfunction "2_16") (pintype "passive"))
      (node (ref "Q14") (pin "3") (pinfunction "C_3") (pintype "passive"))
    )
    (net (code "45") (name "Net-(K14B-P)") (class "Default")
      (node (ref "CONN2P-3.5PI13") (pin "P1") (pinfunction "P1_P1") (pintype "bidirectional"))
      (node (ref "K14") (pin "P1") (pinfunction "P_P1") (pintype "passive"))
    )
    (net (code "46") (name "Net-(K14B-S)") (class "Default")
      (node (ref "CONN2P-3.5PI13") (pin "P0") (pinfunction "P0_P0") (pintype "bidirectional"))
      (node (ref "K14") (pin "S1") (pinfunction "S_S1") (pintype "passive"))
    )
    (net (code "47") (name "Net-(K15A-2)") (class "Default")
      (node (ref "D15") (pin "A") (pinfunction "A_A") (pintype "passive"))
      (node (ref "K15") (pin "16") (pinfunction "2_16") (pintype "passive"))
      (node (ref "Q15") (pin "3") (pinfunction "C_3") (pintype "passive"))
    )
    (net (code "48") (name "Net-(K15B-P)") (class "Default")
      (node (ref "CONN2P-3.5PI14") (pin "P1") (pinfunction "P1_P1") (pintype "bidirectional"))
      (node (ref "K15") (pin "P1") (pinfunction "P_P1") (pintype "passive"))
    )
    (net (code "49") (name "Net-(K15B-S)") (class "Default")
      (node (ref "CONN2P-3.5PI14") (pin "P0") (pinfunction "P0_P0") (pintype "bidirectional"))
      (node (ref "K15") (pin "S1") (pinfunction "S_S1") (pintype "passive"))
    )
    (net (code "50") (name "Net-(Q1-B)") (class "Default")
      (node (ref "Q1") (pin "1") (pinfunction "B_1") (pintype "passive"))
      (node (ref "U3") (pin "3") (pinfunction "ET_3") (pintype "passive"))
    )
    (net (code "51") (name "Net-(Q2-B)") (class "Default")
      (node (ref "Q2") (pin "1") (pinfunction "B_1") (pintype "passive"))
      (node (ref "U5") (pin "3") (pinfunction "ET_3") (pintype "passive"))
    )
    (net (code "52") (name "Net-(Q3-B)") (class "Default")
      (node (ref "Q3") (pin "1") (pinfunction "B_1") (pintype "passive"))
      (node (ref "U6") (pin "3") (pinfunction "ET_3") (pintype "passive"))
    )
    (net (code "53") (name "Net-(Q4-B)") (class "Default")
      (node (ref "Q4") (pin "1") (pinfunction "B_1") (pintype "passive"))
      (node (ref "U7") (pin "3") (pinfunction "ET_3") (pintype "passive"))
    )
    (net (code "54") (name "Net-(Q5-B)") (class "Default")
      (node (ref "Q5") (pin "1") (pinfunction "B_1") (pintype "passive"))
      (node (ref "U8") (pin "3") (pinfunction "ET_3") (pintype "passive"))
    )
    (net (code "55") (name "Net-(Q6-B)") (class "Default")
      (node (ref "Q6") (pin "1") (pinfunction "B_1") (pintype "passive"))
      (node (ref "U9") (pin "3") (pinfunction "ET_3") (pintype "passive"))
    )
    (net (code "56") (name "Net-(Q7-B)") (class "Default")
      (node (ref "Q7") (pin "1") (pinfunction "B_1") (pintype "passive"))
      (node (ref "U10") (pin "3") (pinfunction "ET_3") (pintype "passive"))
    )
    (net (code "57") (name "Net-(Q8-B)") (class "Default")
      (node (ref "Q8") (pin "1") (pinfunction "B_1") (pintype "passive"))
      (node (ref "U11") (pin "3") (pinfunction "ET_3") (pintype "passive"))
    )
    (net (code "58") (name "Net-(Q9-B)") (class "Default")
      (node (ref "Q9") (pin "1") (pinfunction "B_1") (pintype "passive"))
      (node (ref "U12") (pin "3") (pinfunction "ET_3") (pintype "passive"))
    )
    (net (code "59") (name "Net-(Q10-B)") (class "Default")
      (node (ref "Q10") (pin "1") (pinfunction "B_1") (pintype "passive"))
      (node (ref "U13") (pin "3") (pinfunction "ET_3") (pintype "passive"))
    )
    (net (code "60") (name "Net-(Q11-B)") (class "Default")
      (node (ref "Q11") (pin "1") (pinfunction "B_1") (pintype "passive"))
      (node (ref "U14") (pin "3") (pinfunction "ET_3") (pintype "passive"))
    )
    (net (code "61") (name "Net-(Q12-B)") (class "Default")
      (node (ref "Q12") (pin "1") (pinfunction "B_1") (pintype "passive"))
      (node (ref "U15") (pin "3") (pinfunction "ET_3") (pintype "passive"))
    )
    (net (code "62") (name "Net-(Q13-B)") (class "Default")
      (node (ref "Q13") (pin "1") (pinfunction "B_1") (pintype "passive"))
      (node (ref "U16") (pin "3") (pinfunction "ET_3") (pintype "passive"))
    )
    (net (code "63") (name "Net-(Q14-B)") (class "Default")
      (node (ref "Q14") (pin "1") (pinfunction "B_1") (pintype "passive"))
      (node (ref "U17") (pin "3") (pinfunction "ET_3") (pintype "passive"))
    )
    (net (code "64") (name "Net-(Q15-B)") (class "Default")
      (node (ref "Q15") (pin "1") (pinfunction "B_1") (pintype "passive"))
      (node (ref "U18") (pin "3") (pinfunction "ET_3") (pintype "passive"))
    )
    (net (code "65") (name "Net-(U3-A)") (class "Default")
      (node (ref "R6") (pin "2") (pinfunction "2_2") (pintype "passive"))
      (node (ref "U3") (pin "1") (pinfunction "A_1") (pintype "passive"))
    )
    (net (code "66") (name "Net-(U3-CT)") (class "Default")
      (node (ref "R7") (pin "1") (pinfunction "1_1") (pintype "passive"))
      (node (ref "U3") (pin "4") (pinfunction "CT_4") (pintype "passive"))
    )
    (net (code "67") (name "Net-(U5-A)") (class "Default")
      (node (ref "R13") (pin "2") (pinfunction "2_2") (pintype "passive"))
      (node (ref "U5") (pin "1") (pinfunction "A_1") (pintype "passive"))
    )
    (net (code "68") (name "Net-(U5-CT)") (class "Default")
      (node (ref "R14") (pin "1") (pinfunction "1_1") (pintype "passive"))
      (node (ref "U5") (pin "4") (pinfunction "CT_4") (pintype "passive"))
    )
    (net (code "69") (name "Net-(U6-A)") (class "Default")
      (node (ref "R15") (pin "2") (pinfunction "2_2") (pintype "passive"))
      (node (ref "U6") (pin "1") (pinfunction "A_1") (pintype "passive"))
    )
    (net (code "70") (name "Net-(U6-CT)") (class "Default")
      (node (ref "R16") (pin "1") (pinfunction "1_1") (pintype "passive"))
      (node (ref "U6") (pin "4") (pinfunction "CT_4") (pintype "passive"))
    )
    (net (code "71") (name "Net-(U7-A)") (class "Default")
      (node (ref "R17") (pin "2") (pinfunction "2_2") (pintype "passive"))
      (node (ref "U7") (pin "1") (pinfunction "A_1") (pintype "passive"))
    )
    (net (code "72") (name "Net-(U7-CT)") (class "Default")
      (node (ref "R18") (pin "1") (pinfunction "1_1") (pintype "passive"))
      (node (ref "U7") (pin "4") (pinfunction "CT_4") (pintype "passive"))
    )
    (net (code "73") (name "Net-(U8-A)") (class "Default")
      (node (ref "R19") (pin "2") (pinfunction "2_2") (pintype "passive"))
      (node (ref "U8") (pin "1") (pinfunction "A_1") (pintype "passive"))
    )
    (net (code "74") (name "Net-(U8-CT)") (class "Default")
      (node (ref "R20") (pin "1") (pinfunction "1_1") (pintype "passive"))
      (node (ref "U8") (pin "4") (pinfunction "CT_4") (pintype "passive"))
    )
    (net (code "75") (name "Net-(U9-A)") (class "Default")
      (node (ref "R21") (pin "2") (pinfunction "2_2") (pintype "passive"))
      (node (ref "U9") (pin "1") (pinfunction "A_1") (pintype "passive"))
    )
    (net (code "76") (name "Net-(U9-CT)") (class "Default")
      (node (ref "R22") (pin "1") (pinfunction "1_1") (pintype "passive"))
      (node (ref "U9") (pin "4") (pinfunction "CT_4") (pintype "passive"))
    )
    (net (code "77") (name "Net-(U10-A)") (class "Default")
      (node (ref "R23") (pin "2") (pinfunction "2_2") (pintype "passive"))
      (node (ref "U10") (pin "1") (pinfunction "A_1") (pintype "passive"))
    )
    (net (code "78") (name "Net-(U10-CT)") (class "Default")
      (node (ref "R24") (pin "1") (pinfunction "1_1") (pintype "passive"))
      (node (ref "U10") (pin "4") (pinfunction "CT_4") (pintype "passive"))
    )
    (net (code "79") (name "Net-(U11-A)") (class "Default")
      (node (ref "R25") (pin "2") (pinfunction "2_2") (pintype "passive"))
      (node (ref "U11") (pin "1") (pinfunction "A_1") (pintype "passive"))
    )
    (net (code "80") (name "Net-(U11-CT)") (class "Default")
      (node (ref "R26") (pin "1") (pinfunction "1_1") (pintype "passive"))
      (node (ref "U11") (pin "4") (pinfunction "CT_4") (pintype "passive"))
    )
    (net (code "81") (name "Net-(U12-A)") (class "Default")
      (node (ref "R27") (pin "2") (pinfunction "2_2") (pintype "passive"))
      (node (ref "U12") (pin "1") (pinfunction "A_1") (pintype "passive"))
    )
    (net (code "82") (name "Net-(U12-CT)") (class "Default")
      (node (ref "R28") (pin "1") (pinfunction "1_1") (pintype "passive"))
      (node (ref "U12") (pin "4") (pinfunction "CT_4") (pintype "passive"))
    )
    (net (code "83") (name "Net-(U13-A)") (class "Default")
      (node (ref "R29") (pin "2") (pinfunction "2_2") (pintype "passive"))
      (node (ref "U13") (pin "1") (pinfunction "A_1") (pintype "passive"))
    )
    (net (code "84") (name "Net-(U13-CT)") (class "Default")
      (node (ref "R30") (pin "1") (pinfunction "1_1") (pintype "passive"))
      (node (ref "U13") (pin "4") (pinfunction "CT_4") (pintype "passive"))
    )
    (net (code "85") (name "Net-(U14-A)") (class "Default")
      (node (ref "R31") (pin "2") (pinfunction "2_2") (pintype "passive"))
      (node (ref "U14") (pin "1") (pinfunction "A_1") (pintype "passive"))
    )
    (net (code "86") (name "Net-(U14-CT)") (class "Default")
      (node (ref "R32") (pin "1") (pinfunction "1_1") (pintype "passive"))
      (node (ref "U14") (pin "4") (pinfunction "CT_4") (pintype "passive"))
    )
    (net (code "87") (name "Net-(U15-A)") (class "Default")
      (node (ref "R33") (pin "2") (pinfunction "2_2") (pintype "passive"))
      (node (ref "U15") (pin "1") (pinfunction "A_1") (pintype "passive"))
    )
    (net (code "88") (name "Net-(U15-CT)") (class "Default")
      (node (ref "R34") (pin "1") (pinfunction "1_1") (pintype "passive"))
      (node (ref "U15") (pin "4") (pinfunction "CT_4") (pintype "passive"))
    )
    (net (code "89") (name "Net-(U16-A)") (class "Default")
      (node (ref "R35") (pin "2") (pinfunction "2_2") (pintype "passive"))
      (node (ref "U16") (pin "1") (pinfunction "A_1") (pintype "passive"))
    )
    (net (code "90") (name "Net-(U16-CT)") (class "Default")
      (node (ref "R36") (pin "1") (pinfunction "1_1") (pintype "passive"))
      (node (ref "U16") (pin "4") (pinfunction "CT_4") (pintype "passive"))
    )
    (net (code "91") (name "Net-(U17-A)") (class "Default")
      (node (ref "R37") (pin "2") (pinfunction "2_2") (pintype "passive"))
      (node (ref "U17") (pin "1") (pinfunction "A_1") (pintype "passive"))
    )
    (net (code "92") (name "Net-(U17-CT)") (class "Default")
      (node (ref "R38") (pin "1") (pinfunction "1_1") (pintype "passive"))
      (node (ref "U17") (pin "4") (pinfunction "CT_4") (pintype "passive"))
    )
    (net (code "93") (name "Net-(U18-A)") (class "Default")
      (node (ref "R39") (pin "2") (pinfunction "2_2") (pintype "passive"))
      (node (ref "U18") (pin "1") (pinfunction "A_1") (pintype "passive"))
    )
    (net (code "94") (name "Net-(U18-CT)") (class "Default")
      (node (ref "R40") (pin "1") (pinfunction "1_1") (pintype "passive"))
      (node (ref "U18") (pin "4") (pinfunction "CT_4") (pintype "passive"))
    )
    (net (code "95") (name "P1") (class "Default")
      (node (ref "JP1") (pin "1") (pinfunction "1_1") (pintype "passive"))
      (node (ref "R6") (pin "1") (pinfunction "1_1") (pintype "passive"))
    )
    (net (code "96") (name "P2") (class "Default")
      (node (ref "JP1") (pin "2") (pinfunction "2_2") (pintype "passive"))
      (node (ref "R13") (pin "1") (pinfunction "1_1") (pintype "passive"))
    )
    (net (code "97") (name "P3") (class "Default")
      (node (ref "JP1") (pin "3") (pinfunction "3_3") (pintype "passive"))
      (node (ref "R15") (pin "1") (pinfunction "1_1") (pintype "passive"))
    )
    (net (code "98") (name "P4") (class "Default")
      (node (ref "JP1") (pin "4") (pinfunction "4_4") (pintype "passive"))
      (node (ref "R17") (pin "1") (pinfunction "1_1") (pintype "passive"))
    )
    (net (code "99") (name "P5") (class "Default")
      (node (ref "JP1") (pin "5") (pinfunction "5_5") (pintype "passive"))
      (node (ref "R19") (pin "1") (pinfunction "1_1") (pintype "passive"))
    )
    (net (code "100") (name "P6") (class "Default")
      (node (ref "JP1") (pin "6") (pinfunction "6_6") (pintype "passive"))
      (node (ref "R21") (pin "1") (pinfunction "1_1") (pintype "passive"))
    )
    (net (code "101") (name "P7") (class "Default")
      (node (ref "JP1") (pin "7") (pinfunction "7_7") (pintype "passive"))
      (node (ref "R23") (pin "1") (pinfunction "1_1") (pintype "passive"))
    )
    (net (code "102") (name "P8") (class "Default")
      (node (ref "JP1") (pin "8") (pinfunction "8_8") (pintype "passive"))
      (node (ref "R25") (pin "1") (pinfunction "1_1") (pintype "passive"))
    )
    (net (code "103") (name "P9") (class "Default")
      (node (ref "JP1") (pin "9") (pinfunction "9_9") (pintype "passive"))
      (node (ref "R27") (pin "1") (pinfunction "1_1") (pintype "passive"))
    )
    (net (code "104") (name "P10") (class "Default")
      (node (ref "JP1") (pin "10") (pinfunction "10_10") (pintype "passive"))
      (node (ref "R29") (pin "1") (pinfunction "1_1") (pintype "passive"))
    )
    (net (code "105") (name "P11") (class "Default")
      (node (ref "JP1") (pin "11") (pinfunction "11_11") (pintype "passive"))
      (node (ref "R31") (pin "1") (pinfunction "1_1") (pintype "passive"))
    )
    (net (code "106") (name "P12") (class "Default")
      (node (ref "JP1") (pin "12") (pinfunction "12_12") (pintype "passive"))
      (node (ref "R33") (pin "1") (pinfunction "1_1") (pintype "passive"))
    )
    (net (code "107") (name "P13") (class "Default")
      (node (ref "JP1") (pin "13") (pinfunction "13_13") (pintype "passive"))
      (node (ref "R35") (pin "1") (pinfunction "1_1") (pintype "passive"))
    )
    (net (code "108") (name "P14") (class "Default")
      (node (ref "JP1") (pin "14") (pinfunction "14_14") (pintype "passive"))
      (node (ref "R37") (pin "1") (pinfunction "1_1") (pintype "passive"))
    )
    (net (code "109") (name "P15") (class "Default")
      (node (ref "JP1") (pin "15") (pinfunction "15_15") (pintype "passive"))
      (node (ref "R39") (pin "1") (pinfunction "1_1") (pintype "passive"))
    )
    (net (code "110") (name "VCC") (class "Default")
      (node (ref "D1") (pin "C") (pinfunction "K_C") (pintype "passive"))
      (node (ref "D10") (pin "C") (pinfunction "K_C") (pintype "passive"))
      (node (ref "D11") (pin "C") (pinfunction "K_C") (pintype "passive"))
      (node (ref "D12") (pin "C") (pinfunction "K_C") (pintype "passive"))
      (node (ref "D13") (pin "C") (pinfunction "K_C") (pintype "passive"))
      (node (ref "D14") (pin "C") (pinfunction "K_C") (pintype "passive"))
      (node (ref "D15") (pin "C") (pinfunction "K_C") (pintype "passive"))
      (node (ref "D16") (pin "C") (pinfunction "K_C") (pintype "passive"))
      (node (ref "D17") (pin "C") (pinfunction "K_C") (pintype "passive"))
      (node (ref "D2") (pin "C") (pinfunction "K_C") (pintype "passive"))
      (node (ref "D3") (pin "C") (pinfunction "K_C") (pintype "passive"))
      (node (ref "D4") (pin "C") (pinfunction "K_C") (pintype "passive"))
      (node (ref "D5") (pin "C") (pinfunction "K_C") (pintype "passive"))
      (node (ref "D6") (pin "C") (pinfunction "K_C") (pintype "passive"))
      (node (ref "D7") (pin "C") (pinfunction "K_C") (pintype "passive"))
      (node (ref "D8") (pin "C") (pinfunction "K_C") (pintype "passive"))
      (node (ref "D9") (pin "C") (pinfunction "K_C") (pintype "passive"))
      (node (ref "JP1") (pin "17") (pinfunction "17_17") (pintype "passive"))
      (node (ref "K1") (pin "1") (pinfunction "1_1") (pintype "passive"))
      (node (ref "K10") (pin "1") (pinfunction "1_1") (pintype "passive"))
      (node (ref "K11") (pin "1") (pinfunction "1_1") (pintype "passive"))
      (node (ref "K12") (pin "1") (pinfunction "1_1") (pintype "passive"))
      (node (ref "K13") (pin "1") (pinfunction "1_1") (pintype "passive"))
      (node (ref "K14") (pin "1") (pinfunction "1_1") (pintype "passive"))
      (node (ref "K15") (pin "1") (pinfunction "1_1") (pintype "passive"))
      (node (ref "K2") (pin "1") (pinfunction "1_1") (pintype "passive"))
      (node (ref "K3") (pin "1") (pinfunction "1_1") (pintype "passive"))
      (node (ref "K4") (pin "1") (pinfunction "1_1") (pintype "passive"))
      (node (ref "K5") (pin "1") (pinfunction "1_1") (pintype "passive"))
      (node (ref "K6") (pin "1") (pinfunction "1_1") (pintype "passive"))
      (node (ref "K7") (pin "1") (pinfunction "1_1") (pintype "passive"))
      (node (ref "K8") (pin "1") (pinfunction "1_1") (pintype "passive"))
      (node (ref "K9") (pin "1") (pinfunction "1_1") (pintype "passive"))
      (node (ref "R14") (pin "2") (pinfunction "2_2") (pintype "passive"))
      (node (ref "R16") (pin "2") (pinfunction "2_2") (pintype "passive"))
      (node (ref "R18") (pin "2") (pinfunction "2_2") (pintype "passive"))
      (node (ref "R20") (pin "2") (pinfunction "2_2") (pintype "passive"))
      (node (ref "R22") (pin "2") (pinfunction "2_2") (pintype "passive"))
      (node (ref "R24") (pin "2") (pinfunction "2_2") (pintype "passive"))
      (node (ref "R26") (pin "2") (pinfunction "2_2") (pintype "passive"))
      (node (ref "R28") (pin "2") (pinfunction "2_2") (pintype "passive"))
      (node (ref "R30") (pin "2") (pinfunction "2_2") (pintype "passive"))
      (node (ref "R32") (pin "2") (pinfunction "2_2") (pintype "passive"))
      (node (ref "R34") (pin "2") (pinfunction "2_2") (pintype "passive"))
      (node (ref "R36") (pin "2") (pinfunction "2_2") (pintype "passive"))
      (node (ref "R38") (pin "2") (pinfunction "2_2") (pintype "passive"))
      (node (ref "R40") (pin "2") (pinfunction "2_2") (pintype "passive"))
      (node (ref "R7") (pin "2") (pinfunction "2_2") (pintype "passive"))
    )
    (net (code "111") (name "VCC_USB") (class "Default")
      (node (ref "D17") (pin "A") (pinfunction "A_A") (pintype "passive"))
      (node (ref "JP1") (pin "16") (pinfunction "16_16") (pintype "passive"))
    )
    (net (code "112") (name "unconnected-(K1B-O-PadO1)") (class "Default")
      (node (ref "K1") (pin "O1") (pinfunction "O_O1") (pintype "passive"))
    )
    (net (code "113") (name "unconnected-(K1C-O-PadO2)") (class "Default")
      (node (ref "K1") (pin "O2") (pinfunction "O_O2") (pintype "passive"))
    )
    (net (code "114") (name "unconnected-(K1C-P-PadP2)") (class "Default")
      (node (ref "K1") (pin "P2") (pinfunction "P_P2") (pintype "passive"))
    )
    (net (code "115") (name "unconnected-(K1C-S-PadS2)") (class "Default")
      (node (ref "K1") (pin "S2") (pinfunction "S_S2") (pintype "passive"))
    )
    (net (code "116") (name "unconnected-(K2B-O-PadO1)") (class "Default")
      (node (ref "K2") (pin "O1") (pinfunction "O_O1") (pintype "passive"))
    )
    (net (code "117") (name "unconnected-(K2C-O-PadO2)") (class "Default")
      (node (ref "K2") (pin "O2") (pinfunction "O_O2") (pintype "passive"))
    )
    (net (code "118") (name "unconnected-(K2C-P-PadP2)") (class "Default")
      (node (ref "K2") (pin "P2") (pinfunction "P_P2") (pintype "passive"))
    )
    (net (code "119") (name "unconnected-(K2C-S-PadS2)") (class "Default")
      (node (ref "K2") (pin "S2") (pinfunction "S_S2") (pintype "passive"))
    )
    (net (code "120") (name "unconnected-(K3B-O-PadO1)") (class "Default")
      (node (ref "K3") (pin "O1") (pinfunction "O_O1") (pintype "passive"))
    )
    (net (code "121") (name "unconnected-(K3C-O-PadO2)") (class "Default")
      (node (ref "K3") (pin "O2") (pinfunction "O_O2") (pintype "passive"))
    )
    (net (code "122") (name "unconnected-(K3C-P-PadP2)") (class "Default")
      (node (ref "K3") (pin "P2") (pinfunction "P_P2") (pintype "passive"))
    )
    (net (code "123") (name "unconnected-(K3C-S-PadS2)") (class "Default")
      (node (ref "K3") (pin "S2") (pinfunction "S_S2") (pintype "passive"))
    )
    (net (code "124") (name "unconnected-(K4B-O-PadO1)") (class "Default")
      (node (ref "K4") (pin "O1") (pinfunction "O_O1") (pintype "passive"))
    )
    (net (code "125") (name "unconnected-(K4C-O-PadO2)") (class "Default")
      (node (ref "K4") (pin "O2") (pinfunction "O_O2") (pintype "passive"))
    )
    (net (code "126") (name "unconnected-(K4C-P-PadP2)") (class "Default")
      (node (ref "K4") (pin "P2") (pinfunction "P_P2") (pintype "passive"))
    )
    (net (code "127") (name "unconnected-(K4C-S-PadS2)") (class "Default")
      (node (ref "K4") (pin "S2") (pinfunction "S_S2") (pintype "passive"))
    )
    (net (code "128") (name "unconnected-(K5B-O-PadO1)") (class "Default")
      (node (ref "K5") (pin "O1") (pinfunction "O_O1") (pintype "passive"))
    )
    (net (code "129") (name "unconnected-(K5C-O-PadO2)") (class "Default")
      (node (ref "K5") (pin "O2") (pinfunction "O_O2") (pintype "passive"))
    )
    (net (code "130") (name "unconnected-(K5C-P-PadP2)") (class "Default")
      (node (ref "K5") (pin "P2") (pinfunction "P_P2") (pintype "passive"))
    )
    (net (code "131") (name "unconnected-(K5C-S-PadS2)") (class "Default")
      (node (ref "K5") (pin "S2") (pinfunction "S_S2") (pintype "passive"))
    )
    (net (code "132") (name "unconnected-(K6B-O-PadO1)") (class "Default")
      (node (ref "K6") (pin "O1") (pinfunction "O_O1") (pintype "passive"))
    )
    (net (code "133") (name "unconnected-(K6C-O-PadO2)") (class "Default")
      (node (ref "K6") (pin "O2") (pinfunction "O_O2") (pintype "passive"))
    )
    (net (code "134") (name "unconnected-(K6C-P-PadP2)") (class "Default")
      (node (ref "K6") (pin "P2") (pinfunction "P_P2") (pintype "passive"))
    )
    (net (code "135") (name "unconnected-(K6C-S-PadS2)") (class "Default")
      (node (ref "K6") (pin "S2") (pinfunction "S_S2") (pintype "passive"))
    )
    (net (code "136") (name "unconnected-(K7B-O-PadO1)") (class "Default")
      (node (ref "K7") (pin "O1") (pinfunction "O_O1") (pintype "passive"))
    )
    (net (code "137") (name "unconnected-(K7C-O-PadO2)") (class "Default")
      (node (ref "K7") (pin "O2") (pinfunction "O_O2") (pintype "passive"))
    )
    (net (code "138") (name "unconnected-(K7C-P-PadP2)") (class "Default")
      (node (ref "K7") (pin "P2") (pinfunction "P_P2") (pintype "passive"))
    )
    (net (code "139") (name "unconnected-(K7C-S-PadS2)") (class "Default")
      (node (ref "K7") (pin "S2") (pinfunction "S_S2") (pintype "passive"))
    )
    (net (code "140") (name "unconnected-(K8B-O-PadO1)") (class "Default")
      (node (ref "K8") (pin "O1") (pinfunction "O_O1") (pintype "passive"))
    )
    (net (code "141") (name "unconnected-(K8C-O-PadO2)") (class "Default")
      (node (ref "K8") (pin "O2") (pinfunction "O_O2") (pintype "passive"))
    )
    (net (code "142") (name "unconnected-(K8C-P-PadP2)") (class "Default")
      (node (ref "K8") (pin "P2") (pinfunction "P_P2") (pintype "passive"))
    )
    (net (code "143") (name "unconnected-(K8C-S-PadS2)") (class "Default")
      (node (ref "K8") (pin "S2") (pinfunction "S_S2") (pintype "passive"))
    )
    (net (code "144") (name "unconnected-(K9B-O-PadO1)") (class "Default")
      (node (ref "K9") (pin "O1") (pinfunction "O_O1") (pintype "passive"))
    )
    (net (code "145") (name "unconnected-(K9C-O-PadO2)") (class "Default")
      (node (ref "K9") (pin "O2") (pinfunction "O_O2") (pintype "passive"))
    )
    (net (code "146") (name "unconnected-(K9C-P-PadP2)") (class "Default")
      (node (ref "K9") (pin "P2") (pinfunction "P_P2") (pintype "passive"))
    )
    (net (code "147") (name "unconnected-(K9C-S-PadS2)") (class "Default")
      (node (ref "K9") (pin "S2") (pinfunction "S_S2") (pintype "passive"))
    )
    (net (code "148") (name "unconnected-(K10B-O-PadO1)") (class "Default")
      (node (ref "K10") (pin "O1") (pinfunction "O_O1") (pintype "passive"))
    )
    (net (code "149") (name "unconnected-(K10C-O-PadO2)") (class "Default")
      (node (ref "K10") (pin "O2") (pinfunction "O_O2") (pintype "passive"))
    )
    (net (code "150") (name "unconnected-(K10C-P-PadP2)") (class "Default")
      (node (ref "K10") (pin "P2") (pinfunction "P_P2") (pintype "passive"))
    )
    (net (code "151") (name "unconnected-(K10C-S-PadS2)") (class "Default")
      (node (ref "K10") (pin "S2") (pinfunction "S_S2") (pintype "passive"))
    )
    (net (code "152") (name "unconnected-(K11B-O-PadO1)") (class "Default")
      (node (ref "K11") (pin "O1") (pinfunction "O_O1") (pintype "passive"))
    )
    (net (code "153") (name "unconnected-(K11C-O-PadO2)") (class "Default")
      (node (ref "K11") (pin "O2") (pinfunction "O_O2") (pintype "passive"))
    )
    (net (code "154") (name "unconnected-(K11C-P-PadP2)") (class "Default")
      (node (ref "K11") (pin "P2") (pinfunction "P_P2") (pintype "passive"))
    )
    (net (code "155") (name "unconnected-(K11C-S-PadS2)") (class "Default")
      (node (ref "K11") (pin "S2") (pinfunction "S_S2") (pintype "passive"))
    )
    (net (code "156") (name "unconnected-(K12B-O-PadO1)") (class "Default")
      (node (ref "K12") (pin "O1") (pinfunction "O_O1") (pintype "passive"))
    )
    (net (code "157") (name "unconnected-(K12C-O-PadO2)") (class "Default")
      (node (ref "K12") (pin "O2") (pinfunction "O_O2") (pintype "passive"))
    )
    (net (code "158") (name "unconnected-(K12C-P-PadP2)") (class "Default")
      (node (ref "K12") (pin "P2") (pinfunction "P_P2") (pintype "passive"))
    )
    (net (code "159") (name "unconnected-(K12C-S-PadS2)") (class "Default")
      (node (ref "K12") (pin "S2") (pinfunction "S_S2") (pintype "passive"))
    )
    (net (code "160") (name "unconnected-(K13B-O-PadO1)") (class "Default")
      (node (ref "K13") (pin "O1") (pinfunction "O_O1") (pintype "passive"))
    )
    (net (code "161") (name "unconnected-(K13C-O-PadO2)") (class "Default")
      (node (ref "K13") (pin "O2") (pinfunction "O_O2") (pintype "passive"))
    )
    (net (code "162") (name "unconnected-(K13C-P-PadP2)") (class "Default")
      (node (ref "K13") (pin "P2") (pinfunction "P_P2") (pintype "passive"))
    )
    (net (code "163") (name "unconnected-(K13C-S-PadS2)") (class "Default")
      (node (ref "K13") (pin "S2") (pinfunction "S_S2") (pintype "passive"))
    )
    (net (code "164") (name "unconnected-(K14B-O-PadO1)") (class "Default")
      (node (ref "K14") (pin "O1") (pinfunction "O_O1") (pintype "passive"))
    )
    (net (code "165") (name "unconnected-(K14C-O-PadO2)") (class "Default")
      (node (ref "K14") (pin "O2") (pinfunction "O_O2") (pintype "passive"))
    )
    (net (code "166") (name "unconnected-(K14C-P-PadP2)") (class "Default")
      (node (ref "K14") (pin "P2") (pinfunction "P_P2") (pintype "passive"))
    )
    (net (code "167") (name "unconnected-(K14C-S-PadS2)") (class "Default")
      (node (ref "K14") (pin "S2") (pinfunction "S_S2") (pintype "passive"))
    )
    (net (code "168") (name "unconnected-(K15B-O-PadO1)") (class "Default")
      (node (ref "K15") (pin "O1") (pinfunction "O_O1") (pintype "passive"))
    )
    (net (code "169") (name "unconnected-(K15C-O-PadO2)") (class "Default")
      (node (ref "K15") (pin "O2") (pinfunction "O_O2") (pintype "passive"))
    )
    (net (code "170") (name "unconnected-(K15C-P-PadP2)") (class "Default")
      (node (ref "K15") (pin "P2") (pinfunction "P_P2") (pintype "passive"))
    )
    (net (code "171") (name "unconnected-(K15C-S-PadS2)") (class "Default")
      (node (ref "K15") (pin "S2") (pinfunction "S_S2") (pintype "passive"))
    )
  )
)
